# BOOTSTRAP.net
KiCad netlist of a schematic drawn in Altium Designer
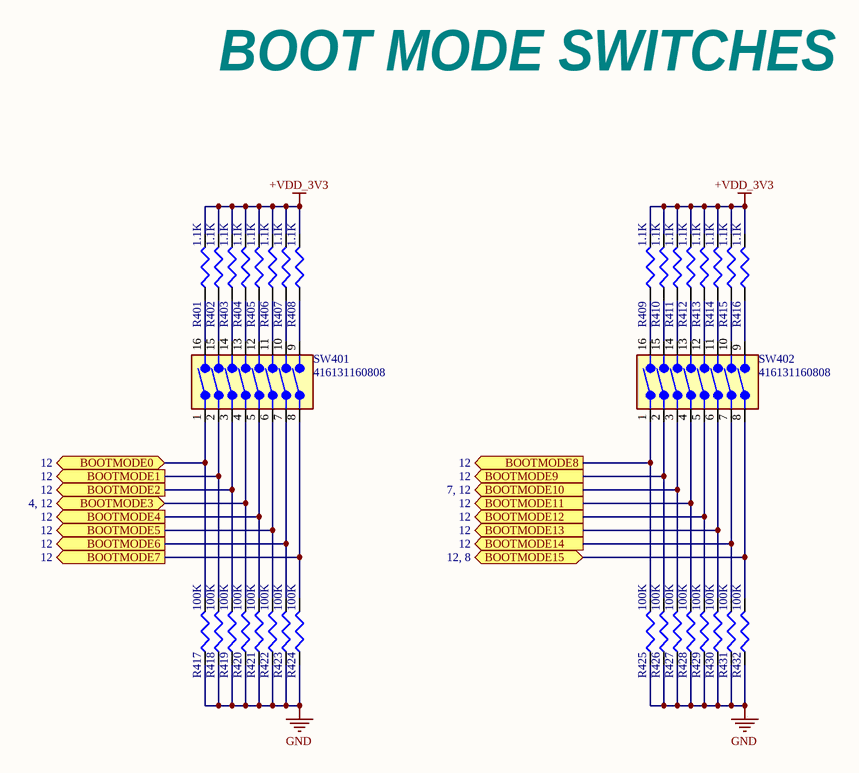
[diagram p0: BOOTSTRAP.SchDoc]

(export (version "E")
  (design (tool "Eeschema 10.0.6"))
  (components
    (comp (ref "R401")
      (value "1.1K")
      (footprint "R0201")
      (description "SMD Chip Resistor, 1.1 kOhm, ± 1%, 50 mW, 0201 [0603 Metric], Thick Film, General Purpose")
      (fields
        (field (name "MANUFACTURER") "Yageo")
        (field (name "MANUFACTURER PART NUMBER") "RC0201FR-071K1L")
      )
      (libsource (lib "Schlib SOM AM625") (part "RC0201FR-071K1L"))
    )
    (comp (ref "R402")
      (value "1.1K")
      (footprint "R0201")
      (description "SMD Chip Resistor, 1.1 kOhm, ± 1%, 50 mW, 0201 [0603 Metric], Thick Film, General Purpose")
      (fields
        (field (name "MANUFACTURER") "Yageo")
        (field (name "MANUFACTURER PART NUMBER") "RC0201FR-071K1L")
      )
      (libsource (lib "Schlib SOM AM625") (part "RC0201FR-071K1L"))
    )
    (comp (ref "R403")
      (value "1.1K")
      (footprint "R0201")
      (description "SMD Chip Resistor, 1.1 kOhm, ± 1%, 50 mW, 0201 [0603 Metric], Thick Film, General Purpose")
      (fields
        (field (name "MANUFACTURER") "Yageo")
        (field (name "MANUFACTURER PART NUMBER") "RC0201FR-071K1L")
      )
      (libsource (lib "Schlib SOM AM625") (part "RC0201FR-071K1L"))
    )
    (comp (ref "R404")
      (value "1.1K")
      (footprint "R0201")
      (description "SMD Chip Resistor, 1.1 kOhm, ± 1%, 50 mW, 0201 [0603 Metric], Thick Film, General Purpose")
      (fields
        (field (name "MANUFACTURER") "Yageo")
        (field (name "MANUFACTURER PART NUMBER") "RC0201FR-071K1L")
      )
      (libsource (lib "Schlib SOM AM625") (part "RC0201FR-071K1L"))
    )
    (comp (ref "R405")
      (value "1.1K")
      (footprint "R0201")
      (description "SMD Chip Resistor, 1.1 kOhm, ± 1%, 50 mW, 0201 [0603 Metric], Thick Film, General Purpose")
      (fields
        (field (name "MANUFACTURER") "Yageo")
        (field (name "MANUFACTURER PART NUMBER") "RC0201FR-071K1L")
      )
      (libsource (lib "Schlib SOM AM625") (part "RC0201FR-071K1L"))
    )
    (comp (ref "R406")
      (value "1.1K")
      (footprint "R0201")
      (description "SMD Chip Resistor, 1.1 kOhm, ± 1%, 50 mW, 0201 [0603 Metric], Thick Film, General Purpose")
      (fields
        (field (name "MANUFACTURER") "Yageo")
        (field (name "MANUFACTURER PART NUMBER") "RC0201FR-071K1L")
      )
      (libsource (lib "Schlib SOM AM625") (part "RC0201FR-071K1L"))
    )
    (comp (ref "R407")
      (value "1.1K")
      (footprint "R0201")
      (description "SMD Chip Resistor, 1.1 kOhm, ± 1%, 50 mW, 0201 [0603 Metric], Thick Film, General Purpose")
      (fields
        (field (name "MANUFACTURER") "Yageo")
        (field (name "MANUFACTURER PART NUMBER") "RC0201FR-071K1L")
      )
      (libsource (lib "Schlib SOM AM625") (part "RC0201FR-071K1L"))
    )
    (comp (ref "R408")
      (value "1.1K")
      (footprint "R0201")
      (description "SMD Chip Resistor, 1.1 kOhm, ± 1%, 50 mW, 0201 [0603 Metric], Thick Film, General Purpose")
      (fields
        (field (name "MANUFACTURER") "Yageo")
        (field (name "MANUFACTURER PART NUMBER") "RC0201FR-071K1L")
      )
      (libsource (lib "Schlib SOM AM625") (part "RC0201FR-071K1L"))
    )
    (comp (ref "R409")
      (value "1.1K")
      (footprint "R0201")
      (description "SMD Chip Resistor, 1.1 kOhm, ± 1%, 50 mW, 0201 [0603 Metric], Thick Film, General Purpose")
      (fields
        (field (name "MANUFACTURER") "Yageo")
        (field (name "MANUFACTURER PART NUMBER") "RC0201FR-071K1L")
      )
      (libsource (lib "Schlib SOM AM625") (part "RC0201FR-071K1L"))
    )
    (comp (ref "R410")
      (value "1.1K")
      (footprint "R0201")
      (description "SMD Chip Resistor, 1.1 kOhm, ± 1%, 50 mW, 0201 [0603 Metric], Thick Film, General Purpose")
      (fields
        (field (name "MANUFACTURER") "Yageo")
        (field (name "MANUFACTURER PART NUMBER") "RC0201FR-071K1L")
      )
      (libsource (lib "Schlib SOM AM625") (part "RC0201FR-071K1L"))
    )
    (comp (ref "R411")
      (value "1.1K")
      (footprint "R0201")
      (description "SMD Chip Resistor, 1.1 kOhm, ± 1%, 50 mW, 0201 [0603 Metric], Thick Film, General Purpose")
      (fields
        (field (name "MANUFACTURER") "Yageo")
        (field (name "MANUFACTURER PART NUMBER") "RC0201FR-071K1L")
      )
      (libsource (lib "Schlib SOM AM625") (part "RC0201FR-071K1L"))
    )
    (comp (ref "R412")
      (value "1.1K")
      (footprint "R0201")
      (description "SMD Chip Resistor, 1.1 kOhm, ± 1%, 50 mW, 0201 [0603 Metric], Thick Film, General Purpose")
      (fields
        (field (name "MANUFACTURER") "Yageo")
        (field (name "MANUFACTURER PART NUMBER") "RC0201FR-071K1L")
      )
      (libsource (lib "Schlib SOM AM625") (part "RC0201FR-071K1L"))
    )
    (comp (ref "R413")
      (value "1.1K")
      (footprint "R0201")
      (description "SMD Chip Resistor, 1.1 kOhm, ± 1%, 50 mW, 0201 [0603 Metric], Thick Film, General Purpose")
      (fields
        (field (name "MANUFACTURER") "Yageo")
        (field (name "MANUFACTURER PART NUMBER") "RC0201FR-071K1L")
      )
      (libsource (lib "Schlib SOM AM625") (part "RC0201FR-071K1L"))
    )
    (comp (ref "R414")
      (value "1.1K")
      (footprint "R0201")
      (description "SMD Chip Resistor, 1.1 kOhm, ± 1%, 50 mW, 0201 [0603 Metric], Thick Film, General Purpose")
      (fields
        (field (name "MANUFACTURER") "Yageo")
        (field (name "MANUFACTURER PART NUMBER") "RC0201FR-071K1L")
      )
      (libsource (lib "Schlib SOM AM625") (part "RC0201FR-071K1L"))
    )
    (comp (ref "R415")
      (value "1.1K")
      (footprint "R0201")
      (description "SMD Chip Resistor, 1.1 kOhm, ± 1%, 50 mW, 0201 [0603 Metric], Thick Film, General Purpose")
      (fields
        (field (name "MANUFACTURER") "Yageo")
        (field (name "MANUFACTURER PART NUMBER") "RC0201FR-071K1L")
      )
      (libsource (lib "Schlib SOM AM625") (part "RC0201FR-071K1L"))
    )
    (comp (ref "R416")
      (value "1.1K")
      (footprint "R0201")
      (description "SMD Chip Resistor, 1.1 kOhm, ± 1%, 50 mW, 0201 [0603 Metric], Thick Film, General Purpose")
      (fields
        (field (name "MANUFACTURER") "Yageo")
        (field (name "MANUFACTURER PART NUMBER") "RC0201FR-071K1L")
      )
      (libsource (lib "Schlib SOM AM625") (part "RC0201FR-071K1L"))
    )
    (comp (ref "R417")
      (value "100K")
      (footprint "R0201")
      (description "SMD Chip Resistor, 100 kOhm, ± 1%, 50 mW, 0201 [0603 Metric], Thick Film, General Purpose")
      (fields
        (field (name "MANUFACTURER") "Yageo")
        (field (name "MANUFACTURER PART NUMBER") "RC0201FR-07100KL")
      )
      (libsource (lib "Schlib SOM AM625") (part "RC0201FR-07100KL"))
    )
    (comp (ref "R418")
      (value "100K")
      (footprint "R0201")
      (description "SMD Chip Resistor, 100 kOhm, ± 1%, 50 mW, 0201 [0603 Metric], Thick Film, General Purpose")
      (fields
        (field (name "MANUFACTURER") "Yageo")
        (field (name "MANUFACTURER PART NUMBER") "RC0201FR-07100KL")
      )
      (libsource (lib "Schlib SOM AM625") (part "RC0201FR-07100KL"))
    )
    (comp (ref "R419")
      (value "100K")
      (footprint "R0201")
      (description "SMD Chip Resistor, 100 kOhm, ± 1%, 50 mW, 0201 [0603 Metric], Thick Film, General Purpose")
      (fields
        (field (name "MANUFACTURER") "Yageo")
        (field (name "MANUFACTURER PART NUMBER") "RC0201FR-07100KL")
      )
      (libsource (lib "Schlib SOM AM625") (part "RC0201FR-07100KL"))
    )
    (comp (ref "R420")
      (value "100K")
      (footprint "R0201")
      (description "SMD Chip Resistor, 100 kOhm, ± 1%, 50 mW, 0201 [0603 Metric], Thick Film, General Purpose")
      (fields
        (field (name "MANUFACTURER") "Yageo")
        (field (name "MANUFACTURER PART NUMBER") "RC0201FR-07100KL")
      )
      (libsource (lib "Schlib SOM AM625") (part "RC0201FR-07100KL"))
    )
    (comp (ref "R421")
      (value "100K")
      (footprint "R0201")
      (description "SMD Chip Resistor, 100 kOhm, ± 1%, 50 mW, 0201 [0603 Metric], Thick Film, General Purpose")
      (fields
        (field (name "MANUFACTURER") "Yageo")
        (field (name "MANUFACTURER PART NUMBER") "RC0201FR-07100KL")
      )
      (libsource (lib "Schlib SOM AM625") (part "RC0201FR-07100KL"))
    )
    (comp (ref "R422")
      (value "100K")
      (footprint "R0201")
      (description "SMD Chip Resistor, 100 kOhm, ± 1%, 50 mW, 0201 [0603 Metric], Thick Film, General Purpose")
      (fields
        (field (name "MANUFACTURER") "Yageo")
        (field (name "MANUFACTURER PART NUMBER") "RC0201FR-07100KL")
      )
      (libsource (lib "Schlib SOM AM625") (part "RC0201FR-07100KL"))
    )
    (comp (ref "R423")
      (value "100K")
      (footprint "R0201")
      (description "SMD Chip Resistor, 100 kOhm, ± 1%, 50 mW, 0201 [0603 Metric], Thick Film, General Purpose")
      (fields
        (field (name "MANUFACTURER") "Yageo")
        (field (name "MANUFACTURER PART NUMBER") "RC0201FR-07100KL")
      )
      (libsource (lib "Schlib SOM AM625") (part "RC0201FR-07100KL"))
    )
    (comp (ref "R424")
      (value "100K")
      (footprint "R0201")
      (description "SMD Chip Resistor, 100 kOhm, ± 1%, 50 mW, 0201 [0603 Metric], Thick Film, General Purpose")
      (fields
        (field (name "MANUFACTURER") "Yageo")
        (field (name "MANUFACTURER PART NUMBER") "RC0201FR-07100KL")
      )
      (libsource (lib "Schlib SOM AM625") (part "RC0201FR-07100KL"))
    )
    (comp (ref "R425")
      (value "100K")
      (footprint "R0201")
      (description "SMD Chip Resistor, 100 kOhm, ± 1%, 50 mW, 0201 [0603 Metric], Thick Film, General Purpose")
      (fields
        (field (name "MANUFACTURER") "Yageo")
        (field (name "MANUFACTURER PART NUMBER") "RC0201FR-07100KL")
      )
      (libsource (lib "Schlib SOM AM625") (part "RC0201FR-07100KL"))
    )
    (comp (ref "R426")
      (value "100K")
      (footprint "R0201")
      (description "SMD Chip Resistor, 100 kOhm, ± 1%, 50 mW, 0201 [0603 Metric], Thick Film, General Purpose")
      (fields
        (field (name "MANUFACTURER") "Yageo")
        (field (name "MANUFACTURER PART NUMBER") "RC0201FR-07100KL")
      )
      (libsource (lib "Schlib SOM AM625") (part "RC0201FR-07100KL"))
    )
    (comp (ref "R427")
      (value "100K")
      (footprint "R0201")
      (description "SMD Chip Resistor, 100 kOhm, ± 1%, 50 mW, 0201 [0603 Metric], Thick Film, General Purpose")
      (fields
        (field (name "MANUFACTURER") "Yageo")
        (field (name "MANUFACTURER PART NUMBER") "RC0201FR-07100KL")
      )
      (libsource (lib "Schlib SOM AM625") (part "RC0201FR-07100KL"))
    )
    (comp (ref "R428")
      (value "100K")
      (footprint "R0201")
      (description "SMD Chip Resistor, 100 kOhm, ± 1%, 50 mW, 0201 [0603 Metric], Thick Film, General Purpose")
      (fields
        (field (name "MANUFACTURER") "Yageo")
        (field (name "MANUFACTURER PART NUMBER") "RC0201FR-07100KL")
      )
      (libsource (lib "Schlib SOM AM625") (part "RC0201FR-07100KL"))
    )
    (comp (ref "R429")
      (value "100K")
      (footprint "R0201")
      (description "SMD Chip Resistor, 100 kOhm, ± 1%, 50 mW, 0201 [0603 Metric], Thick Film, General Purpose")
      (fields
        (field (name "MANUFACTURER") "Yageo")
        (field (name "MANUFACTURER PART NUMBER") "RC0201FR-07100KL")
      )
      (libsource (lib "Schlib SOM AM625") (part "RC0201FR-07100KL"))
    )
    (comp (ref "R430")
      (value "100K")
      (footprint "R0201")
      (description "SMD Chip Resistor, 100 kOhm, ± 1%, 50 mW, 0201 [0603 Metric], Thick Film, General Purpose")
      (fields
        (field (name "MANUFACTURER") "Yageo")
        (field (name "MANUFACTURER PART NUMBER") "RC0201FR-07100KL")
      )
      (libsource (lib "Schlib SOM AM625") (part "RC0201FR-07100KL"))
    )
    (comp (ref "R431")
      (value "100K")
      (footprint "R0201")
      (description "SMD Chip Resistor, 100 kOhm, ± 1%, 50 mW, 0201 [0603 Metric], Thick Film, General Purpose")
      (fields
        (field (name "MANUFACTURER") "Yageo")
        (field (name "MANUFACTURER PART NUMBER") "RC0201FR-07100KL")
      )
      (libsource (lib "Schlib SOM AM625") (part "RC0201FR-07100KL"))
    )
    (comp (ref "R432")
      (value "100K")
      (footprint "R0201")
      (description "SMD Chip Resistor, 100 kOhm, ± 1%, 50 mW, 0201 [0603 Metric], Thick Film, General Purpose")
      (fields
        (field (name "MANUFACTURER") "Yageo")
        (field (name "MANUFACTURER PART NUMBER") "RC0201FR-07100KL")
      )
      (libsource (lib "Schlib SOM AM625") (part "RC0201FR-07100KL"))
    )
    (comp (ref "SW401")
      (value "416131160808")
      (footprint "SW_416131160808")
      (fields (field (name "MANUFACTURER") "Wurth Electronics"))
      (libsource (lib "Schlib SOM AM625") (part "416131160808"))
    )
    (comp (ref "SW402")
      (value "416131160808")
      (footprint "SW_416131160808")
      (fields (field (name "MANUFACTURER") "Wurth Electronics"))
      (libsource (lib "Schlib SOM AM625") (part "416131160808"))
    )
  )
  (nets
    (net (code "1") (name "+VDD_3V3") (class "Default")
      (node (ref "R401") (pin "2") (pinfunction "2_2") (pintype "passive"))
      (node (ref "R402") (pin "2") (pinfunction "2_2") (pintype "passive"))
      (node (ref "R403") (pin "2") (pinfunction "2_2") (pintype "passive"))
      (node (ref "R404") (pin "2") (pinfunction "2_2") (pintype "passive"))
      (node (ref "R405") (pin "2") (pinfunction "2_2") (pintype "passive"))
      (node (ref "R406") (pin "2") (pinfunction "2_2") (pintype "passive"))
      (node (ref "R407") (pin "2") (pinfunction "2_2") (pintype "passive"))
      (node (ref "R408") (pin "2") (pinfunction "2_2") (pintype "passive"))
      (node (ref "R409") (pin "2") (pinfunction "2_2") (pintype "passive"))
      (node (ref "R410") (pin "2") (pinfunction "2_2") (pintype "passive"))
      (node (ref "R411") (pin "2") (pinfunction "2_2") (pintype "passive"))
      (node (ref "R412") (pin "2") (pinfunction "2_2") (pintype "passive"))
      (node (ref "R413") (pin "2") (pinfunction "2_2") (pintype "passive"))
      (node (ref "R414") (pin "2") (pinfunction "2_2") (pintype "passive"))
      (node (ref "R415") (pin "2") (pinfunction "2_2") (pintype "passive"))
      (node (ref "R416") (pin "2") (pinfunction "2_2") (pintype "passive"))
    )
    (net (code "2") (name "/BOOTMODE0") (class "Default")
      (node (ref "R417") (pin "2") (pinfunction "2_2") (pintype "passive"))
      (node (ref "SW401") (pin "1") (pinfunction "1_1") (pintype "passive"))
    )
    (net (code "3") (name "/BOOTMODE1") (class "Default")
      (node (ref "R418") (pin "2") (pinfunction "2_2") (pintype "passive"))
      (node (ref "SW401") (pin "2") (pinfunction "2_2") (pintype "passive"))
    )
    (net (code "4") (name "/BOOTMODE2") (class "Default")
      (node (ref "R419") (pin "2") (pinfunction "2_2") (pintype "passive"))
      (node (ref "SW401") (pin "3") (pinfunction "3_3") (pintype "passive"))
    )
    (net (code "5") (name "/BOOTMODE3") (class "Default")
      (node (ref "R420") (pin "2") (pinfunction "2_2") (pintype "passive"))
      (node (ref "SW401") (pin "4") (pinfunction "4_4") (pintype "passive"))
    )
    (net (code "6") (name "/BOOTMODE4") (class "Default")
      (node (ref "R421") (pin "2") (pinfunction "2_2") (pintype "passive"))
      (node (ref "SW401") (pin "5") (pinfunction "5_5") (pintype "passive"))
    )
    (net (code "7") (name "/BOOTMODE5") (class "Default")
      (node (ref "R422") (pin "2") (pinfunction "2_2") (pintype "passive"))
      (node (ref "SW401") (pin "6") (pinfunction "6_6") (pintype "passive"))
    )
    (net (code "8") (name "/BOOTMODE6") (class "Default")
      (node (ref "R423") (pin "2") (pinfunction "2_2") (pintype "passive"))
      (node (ref "SW401") (pin "7") (pinfunction "7_7") (pintype "passive"))
    )
    (net (code "9") (name "/BOOTMODE7") (class "Default")
      (node (ref "R424") (pin "2") (pinfunction "2_2") (pintype "passive"))
      (node (ref "SW401") (pin "8") (pinfunction "8_8") (pintype "passive"))
    )
    (net (code "10") (name "/BOOTMODE8") (class "Default")
      (node (ref "R425") (pin "2") (pinfunction "2_2") (pintype "passive"))
      (node (ref "SW402") (pin "1") (pinfunction "1_1") (pintype "passive"))
    )
    (net (code "11") (name "/BOOTMODE9") (class "Default")
      (node (ref "R426") (pin "2") (pinfunction "2_2") (pintype "passive"))
      (node (ref "SW402") (pin "2") (pinfunction "2_2") (pintype "passive"))
    )
    (net (code "12") (name "/BOOTMODE10") (class "Default")
      (node (ref "R427") (pin "2") (pinfunction "2_2") (pintype "passive"))
      (node (ref "SW402") (pin "3") (pinfunction "3_3") (pintype "passive"))
    )
    (net (code "13") (name "/BOOTMODE11") (class "Default")
      (node (ref "R428") (pin "2") (pinfunction "2_2") (pintype "passive"))
      (node (ref "SW402") (pin "4") (pinfunction "4_4") (pintype "passive"))
    )
    (net (code "14") (name "/BOOTMODE12") (class "Default")
      (node (ref "R429") (pin "2") (pinfunction "2_2") (pintype "passive"))
      (node (ref "SW402") (pin "5") (pinfunction "5_5") (pintype "passive"))
    )
    (net (code "15") (name "/BOOTMODE13") (class "Default")
      (node (ref "R430") (pin "2") (pinfunction "2_2") (pintype "passive"))
      (node (ref "SW402") (pin "6") (pinfunction "6_6") (pintype "passive"))
    )
    (net (code "16") (name "/BOOTMODE14") (class "Default")
      (node (ref "R431") (pin "2") (pinfunction "2_2") (pintype "passive"))
      (node (ref "SW402") (pin "7") (pinfunction "7_7") (pintype "passive"))
    )
    (net (code "17") (name "/BOOTMODE15") (class "Default")
      (node (ref "R432") (pin "2") (pinfunction "2_2") (pintype "passive"))
      (node (ref "SW402") (pin "8") (pinfunction "8_8") (pintype "passive"))
    )
    (net (code "18") (name "GND") (class "Default")
      (node (ref "R417") (pin "1") (pinfunction "1_1") (pintype "passive"))
      (node (ref "R418") (pin "1") (pinfunction "1_1") (pintype "passive"))
      (node (ref "R419") (pin "1") (pinfunction "1_1") (pintype "passive"))
      (node (ref "R420") (pin "1") (pinfunction "1_1") (pintype "passive"))
      (node (ref "R421") (pin "1") (pinfunction "1_1") (pintype "passive"))
      (node (ref "R422") (pin "1") (pinfunction "1_1") (pintype "passive"))
      (node (ref "R423") (pin "1") (pinfunction "1_1") (pintype "passive"))
      (node (ref "R424") (pin "1") (pinfunction "1_1") (pintype "passive"))
      (node (ref "R425") (pin "1") (pinfunction "1_1") (pintype "passive"))
      (node (ref "R426") (pin "1") (pinfunction "1_1") (pintype "passive"))
      (node (ref "R427") (pin "1") (pinfunction "1_1") (pintype "passive"))
      (node (ref "R428") (pin "1") (pinfunction "1_1") (pintype "passive"))
      (node (ref "R429") (pin "1") (pinfunction "1_1") (pintype "passive"))
      (node (ref "R430") (pin "1") (pinfunction "1_1") (pintype "passive"))
      (node (ref "R431") (pin "1") (pinfunction "1_1") (pintype "passive"))
      (node (ref "R432") (pin "1") (pinfunction "1_1") (pintype "passive"))
    )
    (net (code "19") (name "Net-(R401-Pad1)") (class "Default")
      (node (ref "R401") (pin "1") (pinfunction "1_1") (pintype "passive"))
      (node (ref "SW401") (pin "16") (pinfunction "16_16") (pintype "passive"))
    )
    (net (code "20") (name "Net-(R402-Pad1)") (class "Default")
      (node (ref "R402") (pin "1") (pinfunction "1_1") (pintype "passive"))
      (node (ref "SW401") (pin "15") (pinfunction "15_15") (pintype "passive"))
    )
    (net (code "21") (name "Net-(R403-Pad1)") (class "Default")
      (node (ref "R403") (pin "1") (pinfunction "1_1") (pintype "passive"))
      (node (ref "SW401") (pin "14") (pinfunction "14_14") (pintype "passive"))
    )
    (net (code "22") (name "Net-(R404-Pad1)") (class "Default")
      (node (ref "R404") (pin "1") (pinfunction "1_1") (pintype "passive"))
      (node (ref "SW401") (pin "13") (pinfunction "13_13") (pintype "passive"))
    )
    (net (code "23") (name "Net-(R405-Pad1)") (class "Default")
      (node (ref "R405") (pin "1") (pinfunction "1_1") (pintype "passive"))
      (node (ref "SW401") (pin "12") (pinfunction "12_12") (pintype "passive"))
    )
    (net (code "24") (name "Net-(R406-Pad1)") (class "Default")
      (node (ref "R406") (pin "1") (pinfunction "1_1") (pintype "passive"))
      (node (ref "SW401") (pin "11") (pinfunction "11_11") (pintype "passive"))
    )
    (net (code "25") (name "Net-(R407-Pad1)") (class "Default")
      (node (ref "R407") (pin "1") (pinfunction "1_1") (pintype "passive"))
      (node (ref "SW401") (pin "10") (pinfunction "10_10") (pintype "passive"))
    )
    (net (code "26") (name "Net-(R408-Pad1)") (class "Default")
      (node (ref "R408") (pin "1") (pinfunction "1_1") (pintype "passive"))
      (node (ref "SW401") (pin "9") (pinfunction "9_9") (pintype "passive"))
    )
    (net (code "27") (name "Net-(R409-Pad1)") (class "Default")
      (node (ref "R409") (pin "1") (pinfunction "1_1") (pintype "passive"))
      (node (ref "SW402") (pin "16") (pinfunction "16_16") (pintype "passive"))
    )
    (net (code "28") (name "Net-(R410-Pad1)") (class "Default")
      (node (ref "R410") (pin "1") (pinfunction "1_1") (pintype "passive"))
      (node (ref "SW402") (pin "15") (pinfunction "15_15") (pintype "passive"))
    )
    (net (code "29") (name "Net-(R411-Pad1)") (class "Default")
      (node (ref "R411") (pin "1") (pinfunction "1_1") (pintype "passive"))
      (node (ref "SW402") (pin "14") (pinfunction "14_14") (pintype "passive"))
    )
    (net (code "30") (name "Net-(R412-Pad1)") (class "Default")
      (node (ref "R412") (pin "1") (pinfunction "1_1") (pintype "passive"))
      (node (ref "SW402") (pin "13") (pinfunction "13_13") (pintype "passive"))
    )
    (net (code "31") (name "Net-(R413-Pad1)") (class "Default")
      (node (ref "R413") (pin "1") (pinfunction "1_1") (pintype "passive"))
      (node (ref "SW402") (pin "12") (pinfunction "12_12") (pintype "passive"))
    )
    (net (code "32") (name "Net-(R414-Pad1)") (class "Default")
      (node (ref "R414") (pin "1") (pinfunction "1_1") (pintype "passive"))
      (node (ref "SW402") (pin "11") (pinfunction "11_11") (pintype "passive"))
    )
    (net (code "33") (name "Net-(R415-Pad1)") (class "Default")
      (node (ref "R415") (pin "1") (pinfunction "1_1") (pintype "passive"))
      (node (ref "SW402") (pin "10") (pinfunction "10_10") (pintype "passive"))
    )
    (net (code "34") (name "Net-(R416-Pad1)") (class "Default")
      (node (ref "R416") (pin "1") (pinfunction "1_1") (pintype "passive"))
      (node (ref "SW402") (pin "9") (pinfunction "9_9") (pintype "passive"))
    )
  )
)
